# okinesio_v01.net
KiCad netlist of a schematic drawn in EAGLE
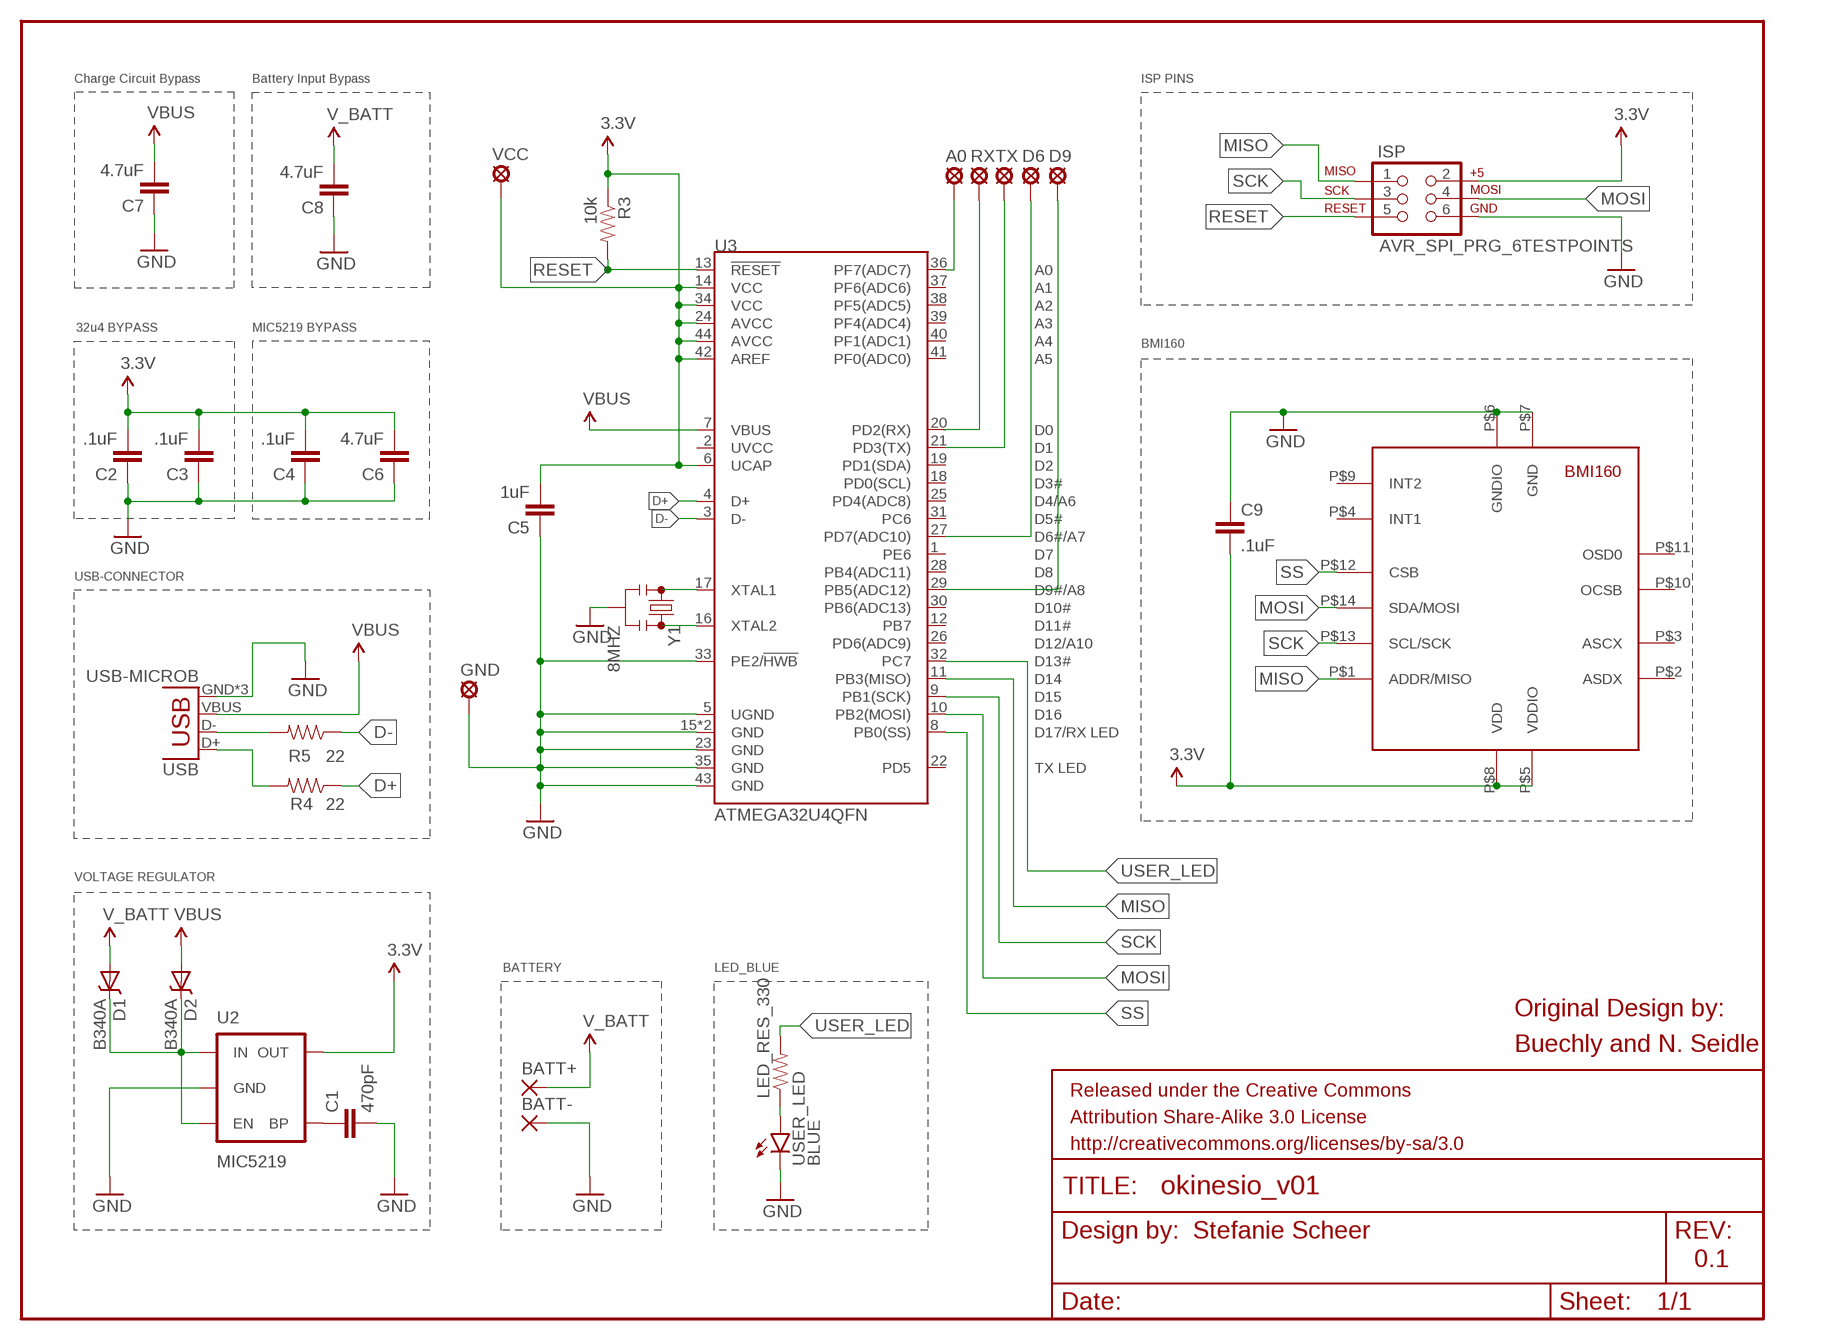
[diagram p0: schematic, sheet 1]

(export (version "E")
  (design (tool "Eeschema 10.0.6"))
  (components
    (comp (ref "A0")
      (value "LSP10")
      (footprint "eagle-import:LSP10")
      (libsource (lib "eagle-import") (part "LSP10"))
    )
    (comp (ref "BATT+")
      (value "SMD2")
      (footprint "eagle-import:SMD1,27-2,54")
      (libsource (lib "eagle-import") (part "SMD2"))
    )
    (comp (ref "BATT-")
      (value "SMD2")
      (footprint "eagle-import:SMD1,27-2,54")
      (libsource (lib "eagle-import") (part "SMD2"))
    )
    (comp (ref "C1")
      (value "470pF")
      (footprint "eagle-import:0603-CAP")
      (libsource (lib "eagle-import") (part "CAP0603-CAP"))
    )
    (comp (ref "C2")
      (value ".1uF")
      (footprint "eagle-import:0603-CAP")
      (libsource (lib "eagle-import") (part "CAP0603-CAP"))
    )
    (comp (ref "C3")
      (value ".1uF")
      (footprint "eagle-import:0603-CAP")
      (libsource (lib "eagle-import") (part "CAP0603-CAP"))
    )
    (comp (ref "C4")
      (value ".1uF")
      (footprint "eagle-import:0603-CAP")
      (libsource (lib "eagle-import") (part "CAP0603-CAP"))
    )
    (comp (ref "C5")
      (value "1uF")
      (footprint "eagle-import:0603-CAP")
      (libsource (lib "eagle-import") (part "CAP0603-CAP"))
    )
    (comp (ref "C6")
      (value "4.7uF")
      (footprint "eagle-import:0603-CAP")
      (libsource (lib "eagle-import") (part "CAP0603-CAP"))
    )
    (comp (ref "C7")
      (value "4.7uF")
      (footprint "eagle-import:1206")
      (libsource (lib "eagle-import") (part "CAP1206"))
    )
    (comp (ref "C8")
      (value "4.7uF")
      (footprint "eagle-import:1206")
      (libsource (lib "eagle-import") (part "CAP1206"))
    )
    (comp (ref "C9")
      (value ".1uF")
      (footprint "eagle-import:0603-CAP")
      (libsource (lib "eagle-import") (part "CAP0603-CAP"))
    )
    (comp (ref "D1")
      (value "B340A")
      (footprint "eagle-import:SMA-DIODE")
      (libsource (lib "eagle-import") (part "DIODE-SCHOTTKY_"))
    )
    (comp (ref "D2")
      (value "B340A")
      (footprint "eagle-import:SMA-DIODE")
      (libsource (lib "eagle-import") (part "DIODE-SCHOTTKY_"))
    )
    (comp (ref "D6")
      (value "LSP10")
      (footprint "eagle-import:LSP10")
      (libsource (lib "eagle-import") (part "LSP10"))
    )
    (comp (ref "D9")
      (value "LSP10")
      (footprint "eagle-import:LSP10")
      (libsource (lib "eagle-import") (part "LSP10"))
    )
    (comp (ref "GND")
      (value "LSP10")
      (footprint "eagle-import:LSP10")
      (libsource (lib "eagle-import") (part "LSP10"))
    )
    (comp (ref "ISP")
      (value "AVR_SPI_PRG_6TESTPOINTS")
      (footprint "eagle-import:2X3_TEST_POINTS")
      (libsource (lib "eagle-import") (part "AVR_SPI_PRG_6TESTPOINTS"))
    )
    (comp (ref "LED_RES_330")
      (value "RESISTOR0603")
      (footprint "eagle-import:0603-RES")
      (libsource (lib "eagle-import") (part "RESISTOR0603"))
    )
    (comp (ref "R3")
      (value "10k")
      (footprint "eagle-import:0603-RES")
      (libsource (lib "eagle-import") (part "RESISTOR0603-RES"))
    )
    (comp (ref "R4")
      (value "22")
      (footprint "eagle-import:0603-RES")
      (libsource (lib "eagle-import") (part "RESISTOR0603-RES"))
    )
    (comp (ref "R5")
      (value "22")
      (footprint "eagle-import:0603-RES")
      (libsource (lib "eagle-import") (part "RESISTOR0603-RES"))
    )
    (comp (ref "RX")
      (value "LSP10")
      (footprint "eagle-import:LSP10")
      (libsource (lib "eagle-import") (part "LSP10"))
    )
    (comp (ref "TX")
      (value "LSP10")
      (footprint "eagle-import:LSP10")
      (libsource (lib "eagle-import") (part "LSP10"))
    )
    (comp (ref "U$3")
      (value "BMI160LGA14")
      (footprint "eagle-import:LGA14-BMI160")
      (libsource (lib "eagle-import") (part "BMI160LGA14"))
    )
    (comp (ref "U2")
      (value "MIC5219")
      (footprint "eagle-import:SOT23-5")
      (libsource (lib "eagle-import") (part "V_REG_MIC5219SMD"))
    )
    (comp (ref "U3")
      (value "ATMEGA32U4QFN")
      (footprint "eagle-import:QFN-44")
      (libsource (lib "eagle-import") (part "ATMEGA32U4QFN"))
    )
    (comp (ref "USB")
      (value "USB-MICROB")
      (footprint "eagle-import:USB-MICROB")
      (libsource (lib "eagle-import") (part "USB-MICROB"))
    )
    (comp (ref "USER_LED")
      (value "BLUE")
      (footprint "eagle-import:LED-0603")
      (libsource (lib "eagle-import") (part "LED-BLUE0603"))
    )
    (comp (ref "VCC")
      (value "LSP10")
      (footprint "eagle-import:LSP10")
      (libsource (lib "eagle-import") (part "LSP10"))
    )
    (comp (ref "Y1")
      (value "8MHZ")
      (footprint "eagle-import:RESONATOR-SMD")
      (libsource (lib "eagle-import") (part "RESONATOR8MHZ"))
    )
  )
  (nets
    (net (code "1") (name "3.3V") (class "Default")
      (node (ref "C2") (pin "2") (pinfunction "2_2") (pintype "passive"))
      (node (ref "C3") (pin "2") (pinfunction "2_2") (pintype "passive"))
      (node (ref "C4") (pin "2") (pinfunction "2_2") (pintype "passive"))
      (node (ref "C5") (pin "2") (pinfunction "2_2") (pintype "passive"))
      (node (ref "C6") (pin "2") (pinfunction "2_2") (pintype "passive"))
      (node (ref "C9") (pin "2") (pinfunction "2_2") (pintype "passive"))
      (node (ref "ISP") (pin "2") (pinfunction "2_2") (pintype "passive"))
      (node (ref "R3") (pin "1") (pinfunction "1_1") (pintype "passive"))
      (node (ref "U$3") (pin "P$5") (pinfunction "VDDIO_P$5") (pintype "bidirectional"))
      (node (ref "U$3") (pin "P$8") (pinfunction "VDD_P$8") (pintype "bidirectional"))
      (node (ref "U2") (pin "5") (pinfunction "OUT_5") (pintype "passive"))
      (node (ref "U3") (pin "14") (pinfunction "VCC_14") (pintype "bidirectional"))
      (node (ref "U3") (pin "24") (pinfunction "AVCC_24") (pintype "bidirectional"))
      (node (ref "U3") (pin "34") (pinfunction "VCC_34") (pintype "bidirectional"))
      (node (ref "U3") (pin "42") (pinfunction "AREF_42") (pintype "bidirectional"))
      (node (ref "U3") (pin "44") (pinfunction "AVCC_44") (pintype "bidirectional"))
      (node (ref "U3") (pin "6") (pinfunction "UCAP_6") (pintype "bidirectional"))
      (node (ref "VCC") (pin "MP") (pinfunction "MP_MP") (pintype "passive"))
    )
    (net (code "2") (name "D+") (class "Default")
      (node (ref "R4") (pin "1") (pinfunction "1_1") (pintype "passive"))
      (node (ref "U3") (pin "4") (pinfunction "D+_4") (pintype "bidirectional"))
    )
    (net (code "3") (name "D-") (class "Default")
      (node (ref "R5") (pin "1") (pinfunction "1_1") (pintype "passive"))
      (node (ref "U3") (pin "3") (pinfunction "D-_3") (pintype "bidirectional"))
    )
    (net (code "4") (name "GND") (class "Default")
      (node (ref "BATT-") (pin "1") (pinfunction "P_1") (pintype "passive"))
      (node (ref "C1") (pin "2") (pinfunction "2_2") (pintype "passive"))
      (node (ref "C2") (pin "1") (pinfunction "1_1") (pintype "passive"))
      (node (ref "C3") (pin "1") (pinfunction "1_1") (pintype "passive"))
      (node (ref "C4") (pin "1") (pinfunction "1_1") (pintype "passive"))
      (node (ref "C5") (pin "1") (pinfunction "1_1") (pintype "passive"))
      (node (ref "C6") (pin "1") (pinfunction "1_1") (pintype "passive"))
      (node (ref "C7") (pin "1") (pinfunction "1_1") (pintype "passive"))
      (node (ref "C8") (pin "1") (pinfunction "1_1") (pintype "passive"))
      (node (ref "C9") (pin "1") (pinfunction "1_1") (pintype "passive"))
      (node (ref "GND") (pin "MP") (pinfunction "MP_MP") (pintype "passive"))
      (node (ref "ISP") (pin "6") (pinfunction "6_6") (pintype "passive"))
      (node (ref "U$3") (pin "P$6") (pinfunction "GNDIO_P$6") (pintype "bidirectional"))
      (node (ref "U$3") (pin "P$7") (pinfunction "GND_P$7") (pintype "bidirectional"))
      (node (ref "U2") (pin "2") (pinfunction "GND_2") (pintype "input"))
      (node (ref "U3") (pin "15") (pinfunction "GND_15") (pintype "bidirectional"))
      (node (ref "U3") (pin "23") (pinfunction "GND_23") (pintype "bidirectional"))
      (node (ref "U3") (pin "33") (pinfunction "PE2/~{HWB}_33") (pintype "bidirectional"))
      (node (ref "U3") (pin "35") (pinfunction "GND_35") (pintype "bidirectional"))
      (node (ref "U3") (pin "43") (pinfunction "GND_43") (pintype "bidirectional"))
      (node (ref "U3") (pin "5") (pinfunction "UGND_5") (pintype "bidirectional"))
      (node (ref "U3") (pin "EPAD") (pinfunction "GND_EPAD") (pintype "bidirectional"))
      (node (ref "USB") (pin "GND") (pinfunction "GND_GND") (pintype "bidirectional"))
      (node (ref "USB") (pin "MT1") (pinfunction "GND_MT1") (pintype "bidirectional"))
      (node (ref "USB") (pin "MT2") (pinfunction "GND_MT2") (pintype "bidirectional"))
      (node (ref "USER_LED") (pin "C") (pinfunction "C_C") (pintype "passive"))
      (node (ref "Y1") (pin "2") (pinfunction "2_2") (pintype "passive"))
    )
    (net (code "5") (name "MISO") (class "Default")
      (node (ref "ISP") (pin "1") (pinfunction "1_1") (pintype "passive"))
      (node (ref "U$3") (pin "P$1") (pinfunction "ADDR/MISO_P$1") (pintype "bidirectional"))
      (node (ref "U3") (pin "11") (pinfunction "PB3(MISO)_11") (pintype "bidirectional"))
    )
    (net (code "6") (name "MOSI") (class "Default")
      (node (ref "ISP") (pin "4") (pinfunction "4_4") (pintype "passive"))
      (node (ref "U$3") (pin "P$14") (pinfunction "SDA/MOSI_P$14") (pintype "bidirectional"))
      (node (ref "U3") (pin "10") (pinfunction "PB2(MOSI)_10") (pintype "bidirectional"))
    )
    (net (code "7") (name "Net-(LED_RES_330-Pad1)") (class "Default")
      (node (ref "LED_RES_330") (pin "1") (pinfunction "1_1") (pintype "passive"))
      (node (ref "USER_LED") (pin "A") (pinfunction "A_A") (pintype "passive"))
    )
    (net (code "8") (name "Net-(R4-Pad2)") (class "Default")
      (node (ref "R4") (pin "2") (pinfunction "2_2") (pintype "passive"))
      (node (ref "USB") (pin "D+") (pinfunction "D+_D+") (pintype "bidirectional"))
    )
    (net (code "9") (name "Net-(R5-Pad2)") (class "Default")
      (node (ref "R5") (pin "2") (pinfunction "2_2") (pintype "passive"))
      (node (ref "USB") (pin "D-") (pinfunction "D-_D-") (pintype "bidirectional"))
    )
    (net (code "10") (name "Net-(U2-BP)") (class "Default")
      (node (ref "C1") (pin "1") (pinfunction "1_1") (pintype "passive"))
      (node (ref "U2") (pin "4") (pinfunction "BP_4") (pintype "input"))
    )
    (net (code "11") (name "Net-(U2-EN)") (class "Default")
      (node (ref "D1") (pin "C") (pinfunction "C_C") (pintype "passive"))
      (node (ref "D2") (pin "C") (pinfunction "C_C") (pintype "passive"))
      (node (ref "U2") (pin "1") (pinfunction "IN_1") (pintype "input"))
      (node (ref "U2") (pin "3") (pinfunction "EN_3") (pintype "input"))
    )
    (net (code "12") (name "Net-(U3-PB5(ADC12))") (class "Default")
      (node (ref "D9") (pin "MP") (pinfunction "MP_MP") (pintype "passive"))
      (node (ref "U3") (pin "29") (pinfunction "PB5(ADC12)_29") (pintype "bidirectional"))
    )
    (net (code "13") (name "Net-(U3-PD2(RX))") (class "Default")
      (node (ref "RX") (pin "MP") (pinfunction "MP_MP") (pintype "passive"))
      (node (ref "U3") (pin "20") (pinfunction "PD2(RX)_20") (pintype "bidirectional"))
    )
    (net (code "14") (name "Net-(U3-PD3(TX))") (class "Default")
      (node (ref "TX") (pin "MP") (pinfunction "MP_MP") (pintype "passive"))
      (node (ref "U3") (pin "21") (pinfunction "PD3(TX)_21") (pintype "bidirectional"))
    )
    (net (code "15") (name "Net-(U3-PD7(ADC10))") (class "Default")
      (node (ref "D6") (pin "MP") (pinfunction "MP_MP") (pintype "passive"))
      (node (ref "U3") (pin "27") (pinfunction "PD7(ADC10)_27") (pintype "bidirectional"))
    )
    (net (code "16") (name "Net-(U3-PF7(ADC7))") (class "Default")
      (node (ref "A0") (pin "MP") (pinfunction "MP_MP") (pintype "passive"))
      (node (ref "U3") (pin "36") (pinfunction "PF7(ADC7)_36") (pintype "bidirectional"))
    )
    (net (code "17") (name "Net-(U3-XTAL1)") (class "Default")
      (node (ref "U3") (pin "17") (pinfunction "XTAL1_17") (pintype "bidirectional"))
      (node (ref "Y1") (pin "1") (pinfunction "1_1") (pintype "passive"))
    )
    (net (code "18") (name "Net-(U3-XTAL2)") (class "Default")
      (node (ref "U3") (pin "16") (pinfunction "XTAL2_16") (pintype "bidirectional"))
      (node (ref "Y1") (pin "3") (pinfunction "3_3") (pintype "passive"))
    )
    (net (code "19") (name "RESET") (class "Default")
      (node (ref "ISP") (pin "5") (pinfunction "5_5") (pintype "passive"))
      (node (ref "R3") (pin "2") (pinfunction "2_2") (pintype "passive"))
      (node (ref "U3") (pin "13") (pinfunction "~{RESET}_13") (pintype "bidirectional"))
    )
    (net (code "20") (name "SCK") (class "Default")
      (node (ref "ISP") (pin "3") (pinfunction "3_3") (pintype "passive"))
      (node (ref "U$3") (pin "P$13") (pinfunction "SCL/SCK_P$13") (pintype "bidirectional"))
      (node (ref "U3") (pin "9") (pinfunction "PB1(SCK)_9") (pintype "bidirectional"))
    )
    (net (code "21") (name "SS") (class "Default")
      (node (ref "U$3") (pin "P$12") (pinfunction "CSB_P$12") (pintype "bidirectional"))
      (node (ref "U3") (pin "8") (pinfunction "PB0(SS)_8") (pintype "bidirectional"))
    )
    (net (code "22") (name "USER_LED") (class "Default")
      (node (ref "LED_RES_330") (pin "2") (pinfunction "2_2") (pintype "passive"))
      (node (ref "U3") (pin "32") (pinfunction "PC7_32") (pintype "bidirectional"))
    )
    (net (code "23") (name "VBUS") (class "Default")
      (node (ref "C7") (pin "2") (pinfunction "2_2") (pintype "passive"))
      (node (ref "D2") (pin "A") (pinfunction "A_A") (pintype "passive"))
      (node (ref "U3") (pin "7") (pinfunction "VBUS_7") (pintype "bidirectional"))
      (node (ref "USB") (pin "VBUS") (pinfunction "VBUS_VBUS") (pintype "bidirectional"))
    )
    (net (code "24") (name "V_BATT") (class "Default")
      (node (ref "BATT+") (pin "1") (pinfunction "P_1") (pintype "passive"))
      (node (ref "C8") (pin "2") (pinfunction "2_2") (pintype "passive"))
      (node (ref "D1") (pin "A") (pinfunction "A_A") (pintype "passive"))
    )
    (net (code "25") (name "unconnected-(U$3-ASCX-PadP$3)") (class "Default")
      (node (ref "U$3") (pin "P$3") (pinfunction "ASCX_P$3") (pintype "bidirectional"))
    )
    (net (code "26") (name "unconnected-(U$3-ASDX-PadP$2)") (class "Default")
      (node (ref "U$3") (pin "P$2") (pinfunction "ASDX_P$2") (pintype "bidirectional"))
    )
    (net (code "27") (name "unconnected-(U$3-INT1-PadP$4)") (class "Default")
      (node (ref "U$3") (pin "P$4") (pinfunction "INT1_P$4") (pintype "bidirectional"))
    )
    (net (code "28") (name "unconnected-(U$3-INT2-PadP$9)") (class "Default")
      (node (ref "U$3") (pin "P$9") (pinfunction "INT2_P$9") (pintype "bidirectional"))
    )
    (net (code "29") (name "unconnected-(U$3-OCSB-PadP$10)") (class "Default")
      (node (ref "U$3") (pin "P$10") (pinfunction "OCSB_P$10") (pintype "bidirectional"))
    )
    (net (code "30") (name "unconnected-(U$3-OSD0-PadP$11)") (class "Default")
      (node (ref "U$3") (pin "P$11") (pinfunction "OSD0_P$11") (pintype "bidirectional"))
    )
    (net (code "31") (name "unconnected-(U3-PB4(ADC11)-Pad28)") (class "Default")
      (node (ref "U3") (pin "28") (pinfunction "PB4(ADC11)_28") (pintype "bidirectional"))
    )
    (net (code "32") (name "unconnected-(U3-PB6(ADC13)-Pad30)") (class "Default")
      (node (ref "U3") (pin "30") (pinfunction "PB6(ADC13)_30") (pintype "bidirectional"))
    )
    (net (code "33") (name "unconnected-(U3-PB7-Pad12)") (class "Default")
      (node (ref "U3") (pin "12") (pinfunction "PB7_12") (pintype "bidirectional"))
    )
    (net (code "34") (name "unconnected-(U3-PC6-Pad31)") (class "Default")
      (node (ref "U3") (pin "31") (pinfunction "PC6_31") (pintype "bidirectional"))
    )
    (net (code "35") (name "unconnected-(U3-PD0(SCL)-Pad18)") (class "Default")
      (node (ref "U3") (pin "18") (pinfunction "PD0(SCL)_18") (pintype "bidirectional"))
    )
    (net (code "36") (name "unconnected-(U3-PD1(SDA)-Pad19)") (class "Default")
      (node (ref "U3") (pin "19") (pinfunction "PD1(SDA)_19") (pintype "bidirectional"))
    )
    (net (code "37") (name "unconnected-(U3-PD4(ADC8)-Pad25)") (class "Default")
      (node (ref "U3") (pin "25") (pinfunction "PD4(ADC8)_25") (pintype "bidirectional"))
    )
    (net (code "38") (name "unconnected-(U3-PD5-Pad22)") (class "Default")
      (node (ref "U3") (pin "22") (pinfunction "PD5_22") (pintype "bidirectional"))
    )
    (net (code "39") (name "unconnected-(U3-PD6(ADC9)-Pad26)") (class "Default")
      (node (ref "U3") (pin "26") (pinfunction "PD6(ADC9)_26") (pintype "bidirectional"))
    )
    (net (code "40") (name "unconnected-(U3-PE6-Pad1)") (class "Default")
      (node (ref "U3") (pin "1") (pinfunction "PE6_1") (pintype "bidirectional"))
    )
    (net (code "41") (name "unconnected-(U3-PF0(ADC0)-Pad41)") (class "Default")
      (node (ref "U3") (pin "41") (pinfunction "PF0(ADC0)_41") (pintype "bidirectional"))
    )
    (net (code "42") (name "unconnected-(U3-PF1(ADC1)-Pad40)") (class "Default")
      (node (ref "U3") (pin "40") (pinfunction "PF1(ADC1)_40") (pintype "bidirectional"))
    )
    (net (code "43") (name "unconnected-(U3-PF4(ADC4)-Pad39)") (class "Default")
      (node (ref "U3") (pin "39") (pinfunction "PF4(ADC4)_39") (pintype "bidirectional"))
    )
    (net (code "44") (name "unconnected-(U3-PF5(ADC5)-Pad38)") (class "Default")
      (node (ref "U3") (pin "38") (pinfunction "PF5(ADC5)_38") (pintype "bidirectional"))
    )
    (net (code "45") (name "unconnected-(U3-PF6(ADC6)-Pad37)") (class "Default")
      (node (ref "U3") (pin "37") (pinfunction "PF6(ADC6)_37") (pintype "bidirectional"))
    )
    (net (code "46") (name "unconnected-(U3-UVCC-Pad2)") (class "Default")
      (node (ref "U3") (pin "2") (pinfunction "UVCC_2") (pintype "bidirectional"))
    )
  )
)
